# Baro.net
KiCad netlist of a schematic drawn in Altium Designer
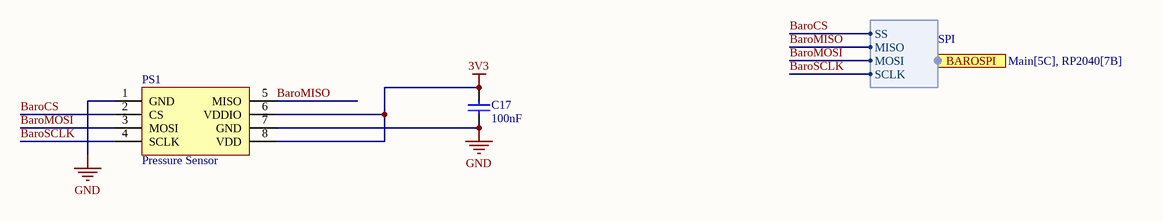
[diagram p0: Baro.SchDoc]

(export (version "E")
  (design (tool "Eeschema 10.0.6"))
  (components
    (comp (ref "C17")
      (value "100nF")
      (footprint "0402 cap")
      (libsource (lib "Custom Components") (part "Capacitor 0402 100nF"))
    )
    (comp (ref "PS1")
      (value "Pressure Sensor")
      (footprint "Goertek SPL06-001")
      (libsource (lib "Custom Components") (part "Goertek SPL06-001"))
    )
  )
  (nets
    (net (code "2") (name "/BaroCS") (class "Default")
      (node (ref "PS1") (pin "2") (pinfunction "CS_2") (pintype "passive"))
    )
    (net (code "3") (name "/BaroMISO") (class "Default")
      (node (ref "PS1") (pin "5") (pinfunction "MISO_5") (pintype "passive"))
    )
    (net (code "4") (name "/BaroMOSI") (class "Default")
      (node (ref "PS1") (pin "3") (pinfunction "MOSI_3") (pintype "passive"))
    )
    (net (code "5") (name "/BaroSCLK") (class "Default")
      (node (ref "PS1") (pin "4") (pinfunction "SCLK_4") (pintype "passive"))
    )
    (net (code "7") (name "3V3") (class "Default")
      (node (ref "C17") (pin "2") (pinfunction "2_2") (pintype "passive"))
      (node (ref "PS1") (pin "6") (pinfunction "VDDIO_6") (pintype "passive"))
      (node (ref "PS1") (pin "8") (pinfunction "VDD_8") (pintype "passive"))
    )
    (net (code "8") (name "GND") (class "Default")
      (node (ref "C17") (pin "1") (pinfunction "1_1") (pintype "passive"))
      (node (ref "PS1") (pin "1") (pinfunction "GND_1") (pintype "passive"))
      (node (ref "PS1") (pin "7") (pinfunction "GND_7") (pintype "passive"))
    )
  )
)
